# electric_fencehigh_voltage_generator.net
KiCad netlist of a schematic drawn in EAGLE
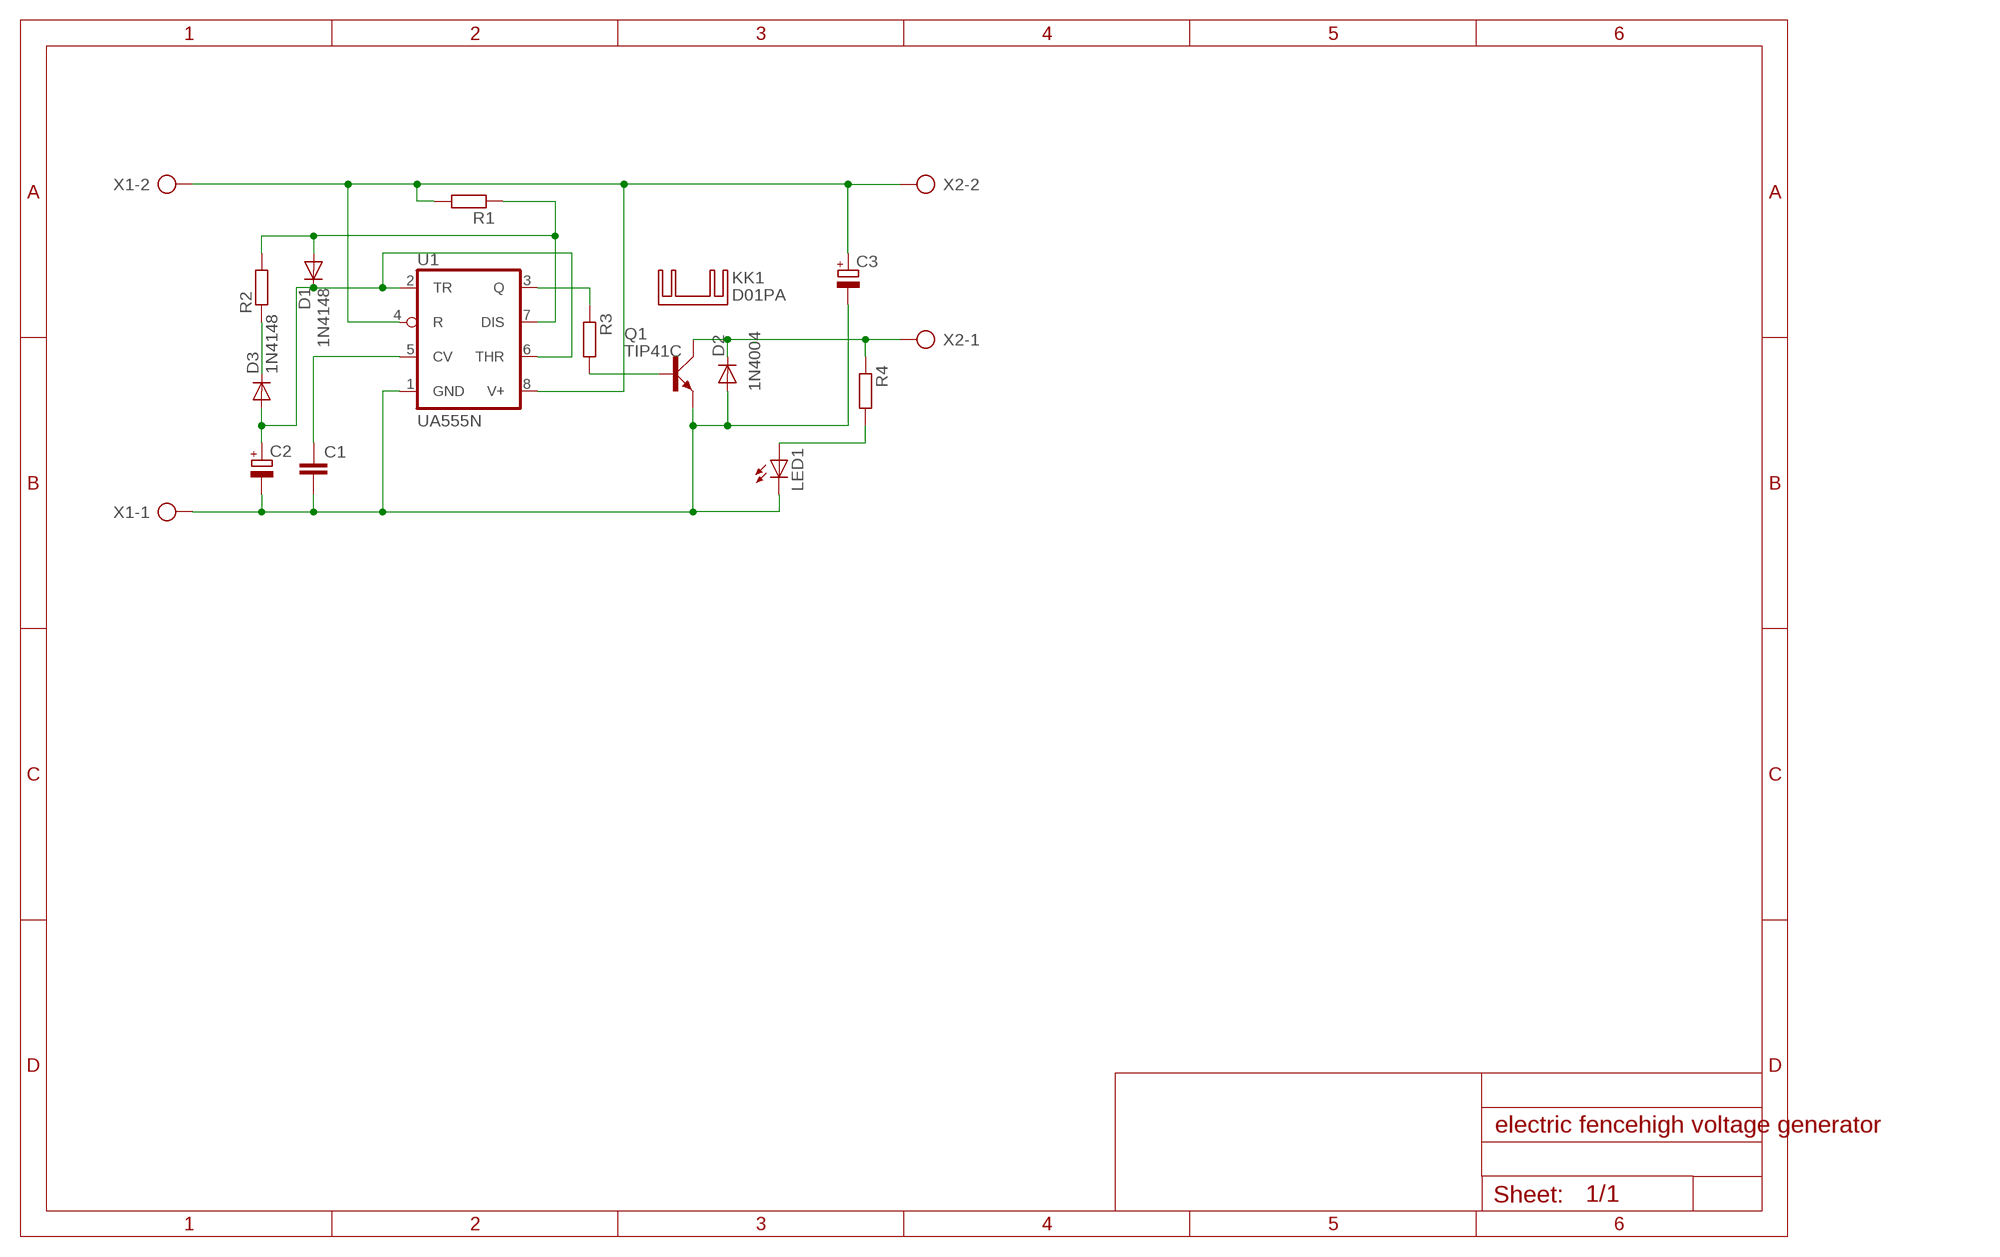
[diagram p0: schematic, sheet 1]

(export (version "E")
  (design (tool "Eeschema 10.0.6"))
  (components
    (comp (ref "C1")
      (value "C-EU050-030X075")
      (footprint "eagle-import:C050-030X075")
      (libsource (lib "eagle-import") (part "C-EU050-030X075"))
    )
    (comp (ref "C2")
      (value "CPOL-EUE2.5-5")
      (footprint "eagle-import:E2,5-5")
      (libsource (lib "eagle-import") (part "CPOL-EUE2.5-5"))
    )
    (comp (ref "C3")
      (value "CPOL-EUE2.5-5")
      (footprint "eagle-import:E2,5-5")
      (libsource (lib "eagle-import") (part "CPOL-EUE2.5-5"))
    )
    (comp (ref "D1")
      (value "1N4148")
      (footprint "eagle-import:DO35-7")
      (libsource (lib "eagle-import") (part "1N4148DO35-7"))
    )
    (comp (ref "D2")
      (value "1N4004")
      (footprint "eagle-import:DO41-10")
      (libsource (lib "eagle-import") (part "1N4004"))
    )
    (comp (ref "D3")
      (value "1N4148")
      (footprint "eagle-import:DO35-7")
      (libsource (lib "eagle-import") (part "1N4148DO35-7"))
    )
    (comp (ref "KK1")
      (value "D01PA")
      (footprint "eagle-import:D01PA")
      (libsource (lib "eagle-import") (part "D01PA"))
    )
    (comp (ref "LED1")
      (value "LED5MM")
      (footprint "eagle-import:LED5MM")
      (libsource (lib "eagle-import") (part "LED5MM"))
    )
    (comp (ref "Q1")
      (value "TIP41C")
      (footprint "eagle-import:TO220AV")
      (libsource (lib "eagle-import") (part "TIP41C"))
    )
    (comp (ref "R1")
      (value "R-EU_0207/10")
      (footprint "eagle-import:0207_10")
      (libsource (lib "eagle-import") (part "R-EU_0207/10"))
    )
    (comp (ref "R2")
      (value "R-EU_0207/10")
      (footprint "eagle-import:0207_10")
      (libsource (lib "eagle-import") (part "R-EU_0207/10"))
    )
    (comp (ref "R3")
      (value "R-EU_0207/15")
      (footprint "eagle-import:0207_15")
      (libsource (lib "eagle-import") (part "R-EU_0207/15"))
    )
    (comp (ref "R4")
      (value "R-EU_0207/10")
      (footprint "eagle-import:0207_10")
      (libsource (lib "eagle-import") (part "R-EU_0207/10"))
    )
    (comp (ref "U1")
      (value "UA555N")
      (footprint "eagle-import:DIL08")
      (libsource (lib "eagle-import") (part "555NUA"))
    )
    (comp (ref "X1")
      (value "AK300/2")
      (footprint "eagle-import:AK300_2")
      (libsource (lib "eagle-import") (part "AK300/2"))
    )
    (comp (ref "X2")
      (value "AK300/2")
      (footprint "eagle-import:AK300_2")
      (libsource (lib "eagle-import") (part "AK300/2"))
    )
  )
  (nets
    (net (code "1") (name "Net-(D3-PadC)") (class "Default")
      (node (ref "D3") (pin "C") (pinfunction "C_C") (pintype "passive"))
      (node (ref "R2") (pin "1") (pinfunction "1_1") (pintype "passive"))
    )
    (net (code "2") (name "Net-(LED1-C)") (class "Default")
      (node (ref "C1") (pin "2") (pinfunction "2_2") (pintype "passive"))
      (node (ref "C2") (pin "-") (pinfunction "-_-") (pintype "passive"))
      (node (ref "C3") (pin "-") (pinfunction "-_-") (pintype "passive"))
      (node (ref "D2") (pin "A") (pinfunction "A_A") (pintype "passive"))
      (node (ref "LED1") (pin "K") (pinfunction "C_K") (pintype "passive"))
      (node (ref "Q1") (pin "E") (pinfunction "E_E") (pintype "passive"))
      (node (ref "U1") (pin "1") (pinfunction "GND_1") (pintype "power_in"))
      (node (ref "X1") (pin "1") (pinfunction "KL_1") (pintype "passive"))
    )
    (net (code "3") (name "Net-(LED1-PadA)") (class "Default")
      (node (ref "LED1") (pin "A") (pinfunction "A_A") (pintype "passive"))
      (node (ref "R4") (pin "2") (pinfunction "2_2") (pintype "passive"))
    )
    (net (code "4") (name "Net-(Q1-PadB)") (class "Default")
      (node (ref "Q1") (pin "B") (pinfunction "B_B") (pintype "passive"))
      (node (ref "R3") (pin "2") (pinfunction "2_2") (pintype "passive"))
    )
    (net (code "5") (name "Net-(U1-CV)") (class "Default")
      (node (ref "C1") (pin "1") (pinfunction "1_1") (pintype "passive"))
      (node (ref "U1") (pin "5") (pinfunction "CV_5") (pintype "input"))
    )
    (net (code "6") (name "Net-(U1-DIS)") (class "Default")
      (node (ref "D1") (pin "A") (pinfunction "A_A") (pintype "passive"))
      (node (ref "R1") (pin "1") (pinfunction "1_1") (pintype "passive"))
      (node (ref "R2") (pin "2") (pinfunction "2_2") (pintype "passive"))
      (node (ref "U1") (pin "7") (pinfunction "DIS_7") (pintype "input"))
    )
    (net (code "7") (name "Net-(U1-Q)") (class "Default")
      (node (ref "R3") (pin "1") (pinfunction "1_1") (pintype "passive"))
      (node (ref "U1") (pin "3") (pinfunction "Q_3") (pintype "output"))
    )
    (net (code "8") (name "Net-(U1-R)") (class "Default")
      (node (ref "C3") (pin "+") (pinfunction "+_+") (pintype "passive"))
      (node (ref "R1") (pin "2") (pinfunction "2_2") (pintype "passive"))
      (node (ref "U1") (pin "4") (pinfunction "R_4") (pintype "input"))
      (node (ref "U1") (pin "8") (pinfunction "V+_8") (pintype "power_in"))
      (node (ref "X1") (pin "2") (pinfunction "KL_2") (pintype "passive"))
      (node (ref "X2") (pin "2") (pinfunction "KL_2") (pintype "passive"))
    )
    (net (code "9") (name "Net-(U1-THR)") (class "Default")
      (node (ref "C2") (pin "+") (pinfunction "+_+") (pintype "passive"))
      (node (ref "D1") (pin "C") (pinfunction "C_C") (pintype "passive"))
      (node (ref "D3") (pin "A") (pinfunction "A_A") (pintype "passive"))
      (node (ref "U1") (pin "2") (pinfunction "TR_2") (pintype "input"))
      (node (ref "U1") (pin "6") (pinfunction "THR_6") (pintype "input"))
    )
    (net (code "10") (name "Net-(X2A-KL)") (class "Default")
      (node (ref "D2") (pin "C") (pinfunction "C_C") (pintype "passive"))
      (node (ref "Q1") (pin "C") (pinfunction "C_C") (pintype "passive"))
      (node (ref "R4") (pin "1") (pinfunction "1_1") (pintype "passive"))
      (node (ref "X2") (pin "1") (pinfunction "KL_1") (pintype "passive"))
    )
  )
)
